# 22.net
KiCad netlist of a schematic drawn in Altium Designer
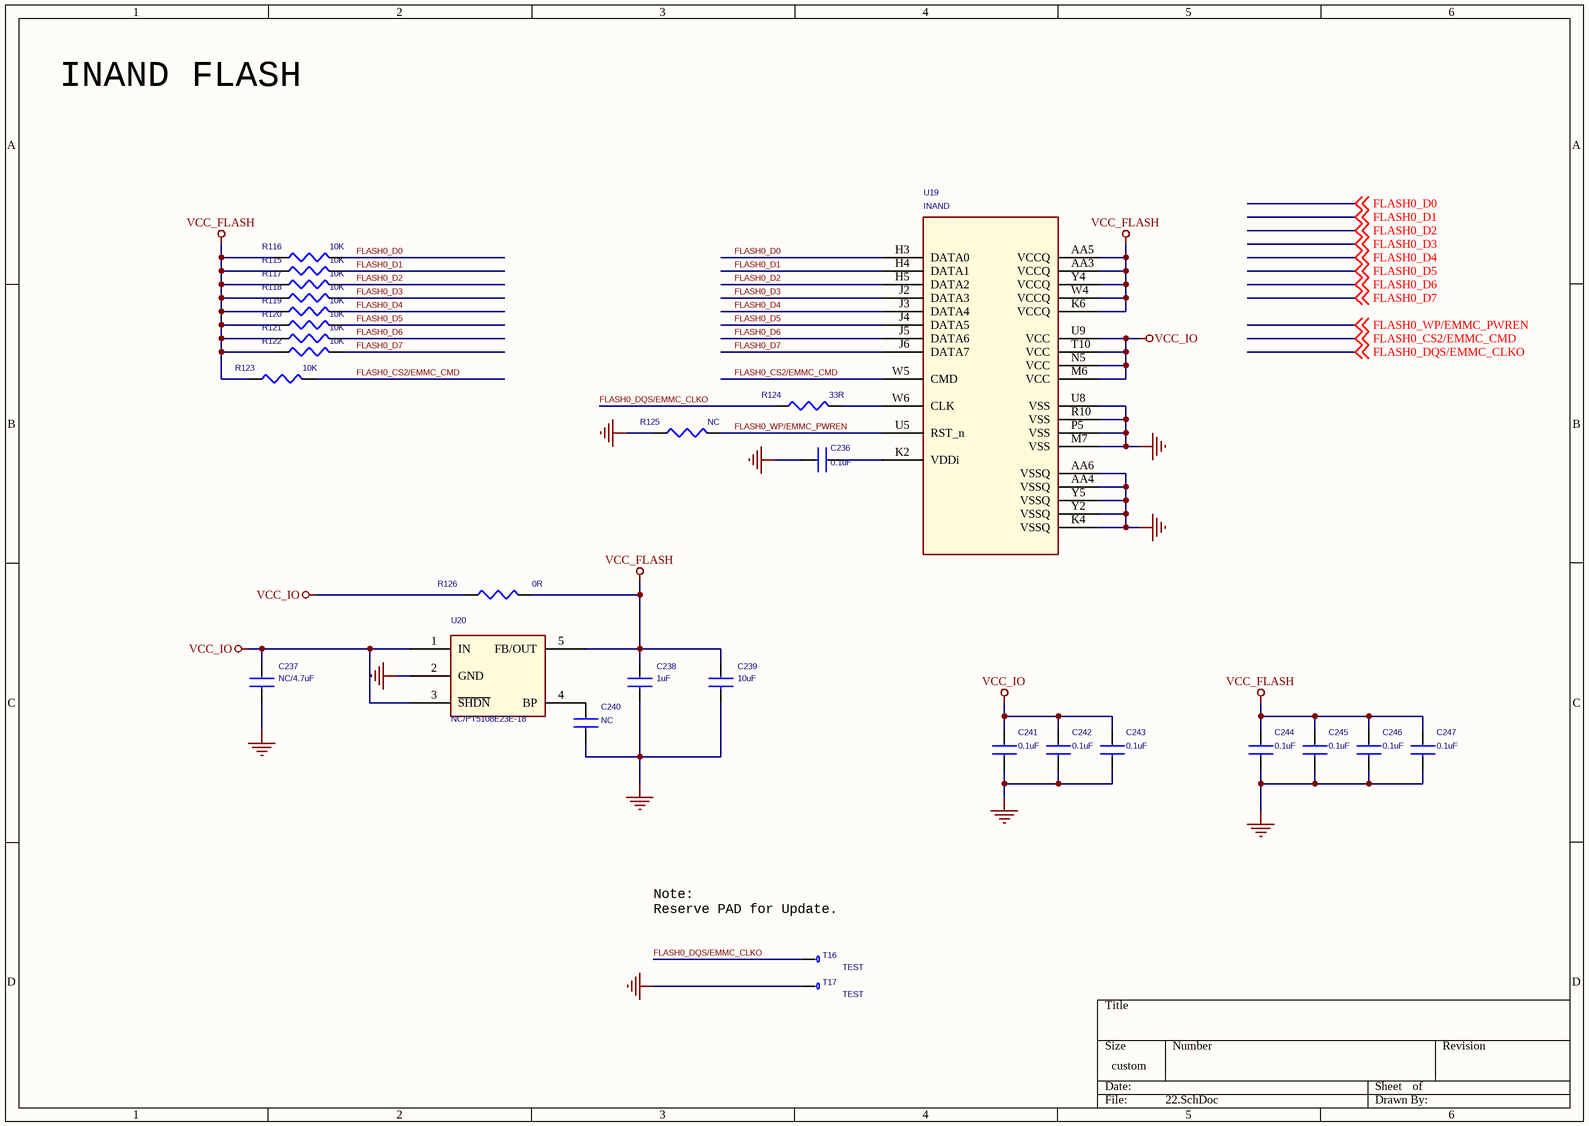
[diagram p0: 22.SchDoc]

(export (version "E")
  (design (tool "Eeschema 10.0.6"))
  (components
    (comp (ref "C236")
      (value "0.1uF")
      (footprint "C0603")
      (description "RoHS CHIP CAP 0.1uF +10/-10% X7R")
      (libsource (lib "*") (part "CAP NP_Dup3"))
    )
    (comp (ref "C237")
      (value "NC/4.7uF")
      (footprint "C0603")
      (description "RoHS CHIP CAP 4.7uF +10/-10% X5R")
      (libsource (lib "*") (part "CAP NP_Dup3"))
    )
    (comp (ref "C238")
      (value "1uF")
      (footprint "C0603")
      (description "RoHS CHIP CAP 4.7uF +10/-10% X5R")
      (libsource (lib "*") (part "CAP NP_Dup3"))
    )
    (comp (ref "C239")
      (value "10uF")
      (footprint "C0603")
      (description "RoHS CHIP CAP 4.7uF +10/-10% X5R")
      (libsource (lib "*") (part "CAP NP_Dup3"))
    )
    (comp (ref "C240")
      (value "NC")
      (footprint "C0603")
      (description "RoHS CHIP CAP 0.1uF +10/-10% X7R")
      (libsource (lib "*") (part "CAP NP_Dup3"))
    )
    (comp (ref "C241")
      (value "0.1uF")
      (footprint "C0603")
      (description "RoHS CHIP CAP 0.1uF +10/-10% X7R")
      (libsource (lib "*") (part "CAP NP_Dup3"))
    )
    (comp (ref "C242")
      (value "0.1uF")
      (footprint "C0603")
      (description "RoHS CHIP CAP 0.1uF +10/-10% X7R")
      (libsource (lib "*") (part "CAP NP_Dup3"))
    )
    (comp (ref "C243")
      (value "0.1uF")
      (footprint "C0603")
      (description "RoHS CHIP CAP 0.1uF +10/-10% X7R")
      (libsource (lib "*") (part "CAP NP_Dup3"))
    )
    (comp (ref "C244")
      (value "0.1uF")
      (footprint "C0603")
      (description "RoHS CHIP CAP 0.1uF +10/-10% X7R")
      (libsource (lib "*") (part "CAP NP_Dup3"))
    )
    (comp (ref "C245")
      (value "0.1uF")
      (footprint "C0603")
      (description "RoHS CHIP CAP 0.1uF +10/-10% X7R")
      (libsource (lib "*") (part "CAP NP_Dup3"))
    )
    (comp (ref "C246")
      (value "0.1uF")
      (footprint "C0603")
      (description "RoHS CHIP CAP 0.1uF +10/-10% X7R")
      (libsource (lib "*") (part "CAP NP_Dup3"))
    )
    (comp (ref "C247")
      (value "0.1uF")
      (footprint "C0603")
      (description "RoHS CHIP CAP 0.1uF +10/-10% X7R")
      (libsource (lib "*") (part "CAP NP_Dup3"))
    )
    (comp (ref "R115")
      (value "10K")
      (footprint "R0402")
      (description "ROHS CHIP RES 10K 1/16W +/-5%")
      (libsource (lib "*") (part "RESISTOR_Dup1"))
    )
    (comp (ref "R116")
      (value "10K")
      (footprint "R0402")
      (description "ROHS CHIP RES 10K 1/16W +/-5%")
      (libsource (lib "*") (part "RESISTOR_Dup1"))
    )
    (comp (ref "R117")
      (value "10K")
      (footprint "R0402")
      (description "ROHS CHIP RES 10K 1/16W +/-5%")
      (libsource (lib "*") (part "RESISTOR_Dup1"))
    )
    (comp (ref "R118")
      (value "10K")
      (footprint "R0402")
      (description "ROHS CHIP RES 10K 1/16W +/-5%")
      (libsource (lib "*") (part "RESISTOR_Dup1"))
    )
    (comp (ref "R119")
      (value "10K")
      (footprint "R0402")
      (description "ROHS CHIP RES 10K 1/16W +/-5%")
      (libsource (lib "*") (part "RESISTOR_Dup1"))
    )
    (comp (ref "R120")
      (value "10K")
      (footprint "R0402")
      (description "ROHS CHIP RES 10K 1/16W +/-5%")
      (libsource (lib "*") (part "RESISTOR_Dup1"))
    )
    (comp (ref "R121")
      (value "10K")
      (footprint "R0402")
      (description "ROHS CHIP RES 10K 1/16W +/-5%")
      (libsource (lib "*") (part "RESISTOR_Dup1"))
    )
    (comp (ref "R122")
      (value "10K")
      (footprint "R0402")
      (description "ROHS CHIP RES 10K 1/16W +/-5%")
      (libsource (lib "*") (part "RESISTOR_Dup1"))
    )
    (comp (ref "R123")
      (value "10K")
      (footprint "R0402")
      (description "ROHS CHIP RES 10K 1/16W +/-5%")
      (libsource (lib "*") (part "RESISTOR_Dup1"))
    )
    (comp (ref "R124")
      (value "33R")
      (footprint "R0402")
      (description "NC")
      (libsource (lib "*") (part "RESISTOR_Dup1"))
    )
    (comp (ref "R125") (value "NC") (footprint "R0402") (libsource (lib "*") (part "RESISTOR_Dup1")))
    (comp (ref "R126")
      (value "0R")
      (footprint "R0402")
      (description "ROHS CHIP RES 10K 1/16W 5%")
      (libsource (lib "*") (part "RESISTOR_Dup1"))
    )
    (comp (ref "T16")
      (value "TEST")
      (footprint "TEST")
      (description "test")
      (libsource (lib "*") (part "TEST_1"))
    )
    (comp (ref "T17")
      (value "TEST")
      (footprint "TEST")
      (description "test")
      (libsource (lib "*") (part "TEST_1"))
    )
    (comp (ref "U19")
      (value "INAND")
      (footprint "INANA-BGA169")
      (description "NAND Flash,H26M54001BKR,2.7V,3.3V,3.6V,128G,N/A,-25℃~85℃,FBGA-169P")
      (libsource (lib "*") (part "INAND"))
    )
    (comp (ref "U20") (value "NC/PT5108E23E-18") (footprint "SOT25") (libsource (lib "*") (part "DS8008_4")))
  )
  (nets
    (net (code "1") (name "FLASH0_CS2{slash}EMMC_CMD") (class "Default")
      (node (ref "R123") (pin "2") (pinfunction "2_2") (pintype "passive"))
      (node (ref "U19") (pin "W5") (pinfunction "CMD_W5") (pintype "passive"))
    )
    (net (code "2") (name "FLASH0_D0") (class "Default")
      (node (ref "R116") (pin "2") (pinfunction "2_2") (pintype "passive"))
      (node (ref "U19") (pin "H3") (pinfunction "DATA0_H3") (pintype "passive"))
    )
    (net (code "3") (name "FLASH0_D1") (class "Default")
      (node (ref "R115") (pin "2") (pinfunction "2_2") (pintype "passive"))
      (node (ref "U19") (pin "H4") (pinfunction "DATA1_H4") (pintype "passive"))
    )
    (net (code "4") (name "FLASH0_D2") (class "Default")
      (node (ref "R117") (pin "2") (pinfunction "2_2") (pintype "passive"))
      (node (ref "U19") (pin "H5") (pinfunction "DATA2_H5") (pintype "passive"))
    )
    (net (code "5") (name "FLASH0_D3") (class "Default")
      (node (ref "R118") (pin "2") (pinfunction "2_2") (pintype "passive"))
      (node (ref "U19") (pin "J2") (pinfunction "DATA3_J2") (pintype "passive"))
    )
    (net (code "6") (name "FLASH0_D4") (class "Default")
      (node (ref "R119") (pin "2") (pinfunction "2_2") (pintype "passive"))
      (node (ref "U19") (pin "J3") (pinfunction "DATA4_J3") (pintype "passive"))
    )
    (net (code "7") (name "FLASH0_D5") (class "Default")
      (node (ref "R120") (pin "2") (pinfunction "2_2") (pintype "passive"))
      (node (ref "U19") (pin "J4") (pinfunction "DATA5_J4") (pintype "passive"))
    )
    (net (code "8") (name "FLASH0_D6") (class "Default")
      (node (ref "R121") (pin "2") (pinfunction "2_2") (pintype "passive"))
      (node (ref "U19") (pin "J5") (pinfunction "DATA6_J5") (pintype "passive"))
    )
    (net (code "9") (name "FLASH0_D7") (class "Default")
      (node (ref "R122") (pin "2") (pinfunction "2_2") (pintype "passive"))
      (node (ref "U19") (pin "J6") (pinfunction "DATA7_J6") (pintype "passive"))
    )
    (net (code "10") (name "FLASH0_DQS{slash}EMMC_CLKO") (class "Default")
      (node (ref "R124") (pin "1") (pinfunction "1_1") (pintype "passive"))
      (node (ref "T16") (pin "1") (pinfunction "1_1") (pintype "passive"))
    )
    (net (code "11") (name "FLASH0_WP{slash}EMMC_PWREN") (class "Default")
      (node (ref "R125") (pin "2") (pinfunction "2_2") (pintype "passive"))
      (node (ref "U19") (pin "U5") (pinfunction "RST_n_U5") (pintype "passive"))
    )
    (net (code "12") (name "GND") (class "Default")
      (node (ref "C236") (pin "1") (pinfunction "1_1") (pintype "passive"))
      (node (ref "C237") (pin "2") (pinfunction "2_2") (pintype "passive"))
      (node (ref "C238") (pin "2") (pinfunction "2_2") (pintype "passive"))
      (node (ref "C239") (pin "2") (pinfunction "2_2") (pintype "passive"))
      (node (ref "C240") (pin "1") (pinfunction "1_1") (pintype "passive"))
      (node (ref "C241") (pin "1") (pinfunction "1_1") (pintype "passive"))
      (node (ref "C242") (pin "1") (pinfunction "1_1") (pintype "passive"))
      (node (ref "C243") (pin "1") (pinfunction "1_1") (pintype "passive"))
      (node (ref "C244") (pin "1") (pinfunction "1_1") (pintype "passive"))
      (node (ref "C245") (pin "1") (pinfunction "1_1") (pintype "passive"))
      (node (ref "C246") (pin "1") (pinfunction "1_1") (pintype "passive"))
      (node (ref "C247") (pin "1") (pinfunction "1_1") (pintype "passive"))
      (node (ref "R125") (pin "1") (pinfunction "1_1") (pintype "passive"))
      (node (ref "T17") (pin "1") (pinfunction "1_1") (pintype "passive"))
      (node (ref "U19") (pin "AA4") (pinfunction "VSSQ_AA4") (pintype "power_in"))
      (node (ref "U19") (pin "AA6") (pinfunction "VSSQ_AA6") (pintype "power_in"))
      (node (ref "U19") (pin "K4") (pinfunction "VSSQ_K4") (pintype "power_in"))
      (node (ref "U19") (pin "M7") (pinfunction "VSS_M7") (pintype "power_in"))
      (node (ref "U19") (pin "P5") (pinfunction "VSS_P5") (pintype "power_in"))
      (node (ref "U19") (pin "R10") (pinfunction "VSS_R10") (pintype "power_in"))
      (node (ref "U19") (pin "U8") (pinfunction "VSS_U8") (pintype "power_in"))
      (node (ref "U19") (pin "Y2") (pinfunction "VSSQ_Y2") (pintype "power_in"))
      (node (ref "U19") (pin "Y5") (pinfunction "VSSQ_Y5") (pintype "power_in"))
      (node (ref "U20") (pin "2") (pinfunction "GND_2") (pintype "passive"))
    )
    (net (code "13") (name "Net-(U19-CLK)") (class "Default")
      (node (ref "R124") (pin "2") (pinfunction "2_2") (pintype "passive"))
      (node (ref "U19") (pin "W6") (pinfunction "CLK_W6") (pintype "passive"))
    )
    (net (code "14") (name "Net-(U19-VDDi)") (class "Default")
      (node (ref "C236") (pin "2") (pinfunction "2_2") (pintype "passive"))
      (node (ref "U19") (pin "K2") (pinfunction "VDDi_K2") (pintype "passive"))
    )
    (net (code "15") (name "Net-(U20-BP)") (class "Default")
      (node (ref "C240") (pin "2") (pinfunction "2_2") (pintype "passive"))
      (node (ref "U20") (pin "4") (pinfunction "BP_4") (pintype "passive"))
    )
    (net (code "16") (name "VCC_FLASH") (class "Default")
      (node (ref "C238") (pin "1") (pinfunction "1_1") (pintype "passive"))
      (node (ref "C239") (pin "1") (pinfunction "1_1") (pintype "passive"))
      (node (ref "C244") (pin "2") (pinfunction "2_2") (pintype "passive"))
      (node (ref "C245") (pin "2") (pinfunction "2_2") (pintype "passive"))
      (node (ref "C246") (pin "2") (pinfunction "2_2") (pintype "passive"))
      (node (ref "C247") (pin "2") (pinfunction "2_2") (pintype "passive"))
      (node (ref "R115") (pin "1") (pinfunction "1_1") (pintype "passive"))
      (node (ref "R116") (pin "1") (pinfunction "1_1") (pintype "passive"))
      (node (ref "R117") (pin "1") (pinfunction "1_1") (pintype "passive"))
      (node (ref "R118") (pin "1") (pinfunction "1_1") (pintype "passive"))
      (node (ref "R119") (pin "1") (pinfunction "1_1") (pintype "passive"))
      (node (ref "R120") (pin "1") (pinfunction "1_1") (pintype "passive"))
      (node (ref "R121") (pin "1") (pinfunction "1_1") (pintype "passive"))
      (node (ref "R122") (pin "1") (pinfunction "1_1") (pintype "passive"))
      (node (ref "R123") (pin "1") (pinfunction "1_1") (pintype "passive"))
      (node (ref "R126") (pin "2") (pinfunction "2_2") (pintype "passive"))
      (node (ref "U19") (pin "AA3") (pinfunction "VCCQ_AA3") (pintype "power_in"))
      (node (ref "U19") (pin "AA5") (pinfunction "VCCQ_AA5") (pintype "power_in"))
      (node (ref "U19") (pin "K6") (pinfunction "VCCQ_K6") (pintype "power_in"))
      (node (ref "U19") (pin "W4") (pinfunction "VCCQ_W4") (pintype "power_in"))
      (node (ref "U19") (pin "Y4") (pinfunction "VCCQ_Y4") (pintype "power_in"))
      (node (ref "U20") (pin "5") (pinfunction "FB/OUT_5") (pintype "passive"))
    )
    (net (code "17") (name "VCC_IO") (class "Default")
      (node (ref "C237") (pin "1") (pinfunction "1_1") (pintype "passive"))
      (node (ref "C241") (pin "2") (pinfunction "2_2") (pintype "passive"))
      (node (ref "C242") (pin "2") (pinfunction "2_2") (pintype "passive"))
      (node (ref "C243") (pin "2") (pinfunction "2_2") (pintype "passive"))
      (node (ref "R126") (pin "1") (pinfunction "1_1") (pintype "passive"))
      (node (ref "U19") (pin "M6") (pinfunction "VCC_M6") (pintype "power_in"))
      (node (ref "U19") (pin "N5") (pinfunction "VCC_N5") (pintype "power_in"))
      (node (ref "U19") (pin "T10") (pinfunction "VCC_T10") (pintype "power_in"))
      (node (ref "U19") (pin "U9") (pinfunction "VCC_U9") (pintype "power_in"))
      (node (ref "U20") (pin "1") (pinfunction "IN_1") (pintype "passive"))
      (node (ref "U20") (pin "3") (pinfunction "~{SHDN}_3") (pintype "passive"))
    )
  )
)
